# AutoProgram.net
KiCad netlist of a schematic drawn in Altium Designer
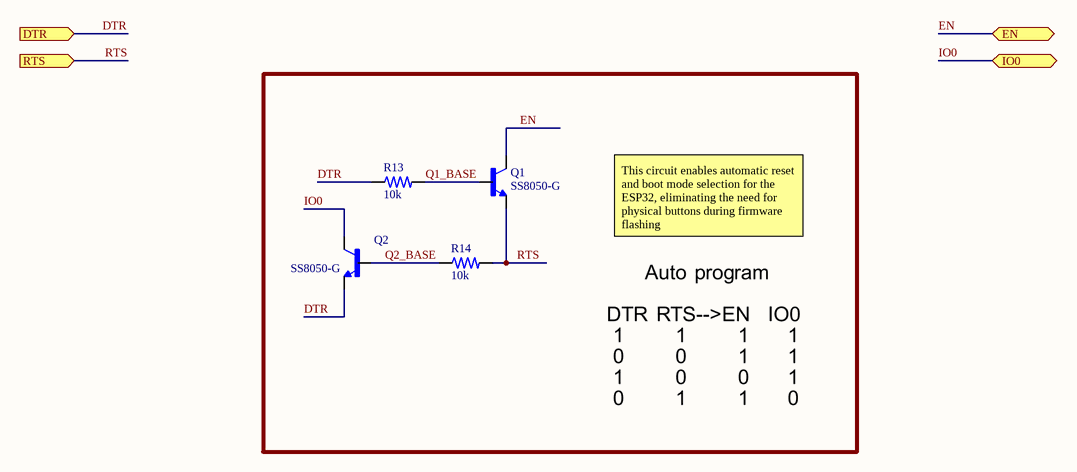
[diagram p0: AutoProgram.SchDoc]

(export (version "E")
  (design (tool "Eeschema 10.0.6"))
  (components
    (comp (ref "Q1")
      (value "SS8050-G")
      (footprint "TRANS_SS8050-G")
      (description "Bipolar (BJT) Transistor NPN 25 V 1.5 A 100MHz 300 mW Surface Mount SOT-23-3")
      (fields (field (name "DIGI-KEY_PART_NUMBER") "641-1790-2-ND") (field (name "MP") "SS8050G"))
      (libsource (lib "Integrated_Library") (part "SS8050-G"))
    )
    (comp (ref "Q2")
      (value "SS8050-G")
      (footprint "TRANS_SS8050-G")
      (description "Bipolar (BJT) Transistor NPN 25 V 1.5 A 100MHz 300 mW Surface Mount SOT-23-3")
      (fields (field (name "DIGI-KEY_PART_NUMBER") "641-1790-2-ND") (field (name "MP") "SS8050G"))
      (libsource (lib "") (part "SS8050-G_1"))
    )
    (comp (ref "R13")
      (value "10k")
      (footprint "0402 RES")
      (description "Res Thick Film 0402 10K Ohm 5% 0.125W(1/8W) ±200ppm/C Pad SMD T/R")
      (fields
        (field (name "MANUFACTURER") "Yageo")
        (field (name "MANUFACTURER PART NUMBER") "RC0402JR-7W10KL")
      )
      (libsource (lib "Integrated_Library") (part "0402 SMD Resistor"))
    )
    (comp (ref "R14")
      (value "10k")
      (footprint "0402 RES")
      (description "Res Thick Film 0402 10K Ohm 5% 0.125W(1/8W) ±200ppm/C Pad SMD T/R")
      (fields
        (field (name "MANUFACTURER") "Yageo")
        (field (name "MANUFACTURER PART NUMBER") "RC0402JR-7W10KL")
      )
      (libsource (lib "Integrated_Library") (part "0402 SMD Resistor"))
    )
  )
  (nets
    (net (code "1") (name "/DTR") (class "Default")
      (node (ref "Q2") (pin "2") (pinfunction "E_2") (pintype "passive"))
      (node (ref "R13") (pin "1") (pinfunction "1_1") (pintype "passive"))
    )
    (net (code "2") (name "/EN") (class "Default")
      (node (ref "Q1") (pin "3") (pinfunction "C_3") (pintype "passive"))
    )
    (net (code "3") (name "/IO0") (class "Default")
      (node (ref "Q2") (pin "3") (pinfunction "C_3") (pintype "passive"))
    )
    (net (code "4") (name "/Q1_BASE") (class "Default")
      (node (ref "Q1") (pin "1") (pinfunction "B_1") (pintype "passive"))
      (node (ref "R13") (pin "2") (pinfunction "2_2") (pintype "passive"))
    )
    (net (code "5") (name "/Q2_BASE") (class "Default")
      (node (ref "Q2") (pin "1") (pinfunction "B_1") (pintype "passive"))
      (node (ref "R14") (pin "1") (pinfunction "1_1") (pintype "passive"))
    )
    (net (code "6") (name "/RTS") (class "Default")
      (node (ref "Q1") (pin "2") (pinfunction "E_2") (pintype "passive"))
      (node (ref "R14") (pin "2") (pinfunction "2_2") (pintype "passive"))
    )
  )
)
